# SERIALIO.net
KiCad netlist of a schematic drawn in Altium Designer
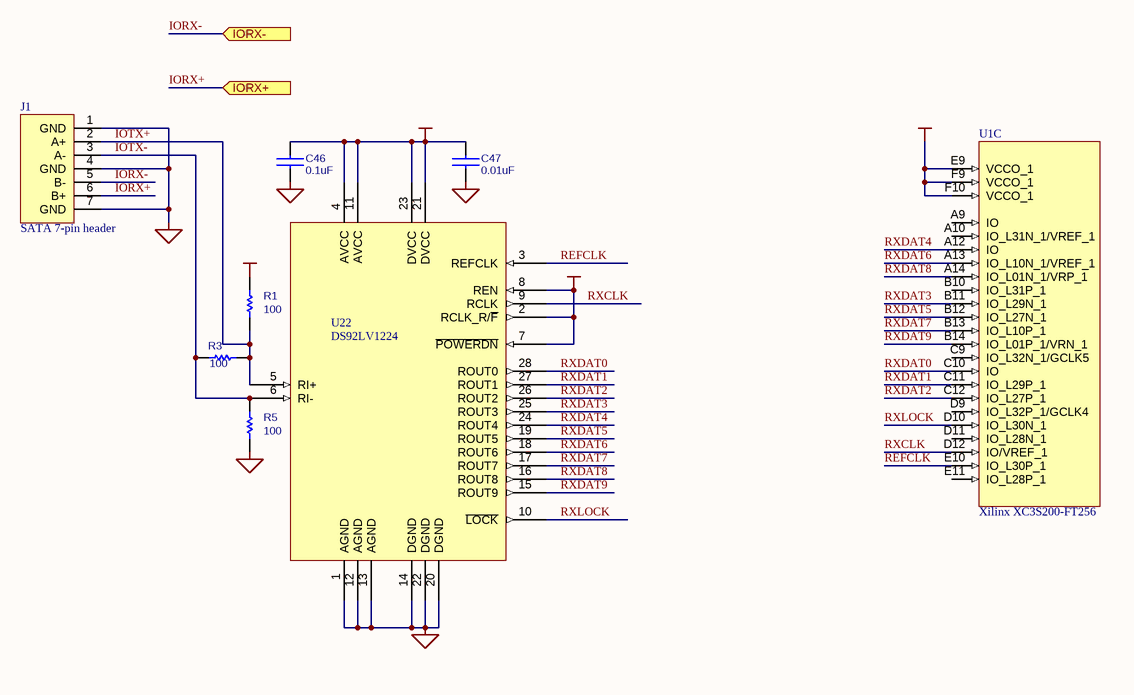
[diagram p0: SERIALIO.SCHDOC]

(export (version "E")
  (design (tool "Eeschema 10.0.6"))
  (components
    (comp (ref "C46")
      (value "0.1uF")
      (footprint "0603")
      (description "Standard Capacitor")
      (fields (field (name "Comment") "CAPACITOR"))
      (libsource (lib "parts") (part "CAPACITOR"))
    )
    (comp (ref "C47")
      (value "0.01uF")
      (footprint "0402")
      (description "Standard Capacitor")
      (fields (field (name "Comment") "CAPACITOR"))
      (libsource (lib "parts") (part "CAPACITOR"))
    )
    (comp (ref "J1")
      (value "SATA 7-pin header")
      (footprint "MOLES 67800-5005")
      (libsource (lib "parts") (part "SATA-7"))
    )
    (comp (ref "R1")
      (value "100")
      (footprint "0603")
      (description "Standard Passive Resistor")
      (fields (field (name "TOLERANCE") "1%"))
      (libsource (lib "parts") (part "RESISTOR"))
    )
    (comp (ref "R3")
      (value "100")
      (footprint "0603")
      (description "Standard Passive Resistor")
      (fields (field (name "TOLERANCE") "1%"))
      (libsource (lib "parts") (part "RESISTOR"))
    )
    (comp (ref "R5")
      (value "100")
      (footprint "0603")
      (description "Standard Passive Resistor")
      (fields (field (name "TOLERANCE") "1%"))
      (libsource (lib "parts") (part "RESISTOR"))
    )
    (comp (ref "U1")
      (value "Xilinx XC3S200-FT256")
      (footprint "Xilinx FT256 BGA")
      (description "Xilinx Spartan-3 FPGA")
      (libsource (lib "parts") (part "XC3S200-FT256"))
    )
    (comp (ref "U22")
      (value "DS92LV1224")
      (footprint "SSO-G28/E4.3")
      (description "30-66 MHz 10-Bit Bus LVDS Deserializer")
      (libsource (lib "parts") (part "DS92LV1224"))
    )
  )
  (nets
    (net (code "1") (name "/IORX+") (class "Default")
      (node (ref "J1") (pin "6") (pinfunction "B+_6") (pintype "passive"))
    )
    (net (code "2") (name "/IORX-") (class "Default")
      (node (ref "J1") (pin "5") (pinfunction "B-_5") (pintype "passive"))
    )
    (net (code "3") (name "/IOTX+") (class "Default")
      (node (ref "J1") (pin "2") (pinfunction "A+_2") (pintype "passive"))
      (node (ref "R1") (pin "2") (pintype "passive"))
      (node (ref "R3") (pin "2") (pintype "passive"))
      (node (ref "U22") (pin "5") (pinfunction "RI+_5") (pintype "input"))
    )
    (net (code "4") (name "/IOTX-") (class "Default")
      (node (ref "J1") (pin "3") (pinfunction "A-_3") (pintype "passive"))
      (node (ref "R3") (pin "1") (pintype "passive"))
      (node (ref "R5") (pin "2") (pintype "passive"))
      (node (ref "U22") (pin "6") (pinfunction "RI-_6") (pintype "input"))
    )
    (net (code "5") (name "/REFCLK") (class "Default")
      (node (ref "U1") (pin "E10") (pinfunction "IO_L30P_1_E10") (pintype "input"))
      (node (ref "U22") (pin "3") (pinfunction "REFCLK_3") (pintype "input"))
    )
    (net (code "6") (name "/RXCLK") (class "Default")
      (node (ref "U1") (pin "D12") (pinfunction "IO/VREF_1_D12") (pintype "input"))
      (node (ref "U22") (pin "9") (pinfunction "RCLK_9") (pintype "output"))
    )
    (net (code "7") (name "/RXDAT0") (class "Default")
      (node (ref "U1") (pin "C10") (pinfunction "IO_C10") (pintype "input"))
      (node (ref "U22") (pin "28") (pinfunction "ROUT0_28") (pintype "output"))
    )
    (net (code "8") (name "/RXDAT1") (class "Default")
      (node (ref "U1") (pin "C11") (pinfunction "IO_L29P_1_C11") (pintype "input"))
      (node (ref "U22") (pin "27") (pinfunction "ROUT1_27") (pintype "output"))
    )
    (net (code "9") (name "/RXDAT2") (class "Default")
      (node (ref "U1") (pin "C12") (pinfunction "IO_L27P_1_C12") (pintype "input"))
      (node (ref "U22") (pin "26") (pinfunction "ROUT2_26") (pintype "output"))
    )
    (net (code "10") (name "/RXDAT3") (class "Default")
      (node (ref "U1") (pin "B11") (pinfunction "IO_L29N_1_B11") (pintype "input"))
      (node (ref "U22") (pin "25") (pinfunction "ROUT3_25") (pintype "output"))
    )
    (net (code "11") (name "/RXDAT4") (class "Default")
      (node (ref "U1") (pin "A12") (pinfunction "IO_A12") (pintype "input"))
      (node (ref "U22") (pin "24") (pinfunction "ROUT4_24") (pintype "output"))
    )
    (net (code "12") (name "/RXDAT5") (class "Default")
      (node (ref "U1") (pin "B12") (pinfunction "IO_L27N_1_B12") (pintype "input"))
      (node (ref "U22") (pin "19") (pinfunction "ROUT5_19") (pintype "output"))
    )
    (net (code "13") (name "/RXDAT6") (class "Default")
      (node (ref "U1") (pin "A13") (pinfunction "IO_L10N_1/VREF_1_A13") (pintype "input"))
      (node (ref "U22") (pin "18") (pinfunction "ROUT6_18") (pintype "output"))
    )
    (net (code "14") (name "/RXDAT7") (class "Default")
      (node (ref "U1") (pin "B13") (pinfunction "IO_L10P_1_B13") (pintype "input"))
      (node (ref "U22") (pin "17") (pinfunction "ROUT7_17") (pintype "output"))
    )
    (net (code "15") (name "/RXDAT8") (class "Default")
      (node (ref "U1") (pin "A14") (pinfunction "IO_L01N_1/VRP_1_A14") (pintype "input"))
      (node (ref "U22") (pin "16") (pinfunction "ROUT8_16") (pintype "output"))
    )
    (net (code "16") (name "/RXDAT9") (class "Default")
      (node (ref "U1") (pin "B14") (pinfunction "IO_L01P_1/VRN_1_B14") (pintype "input"))
      (node (ref "U22") (pin "15") (pinfunction "ROUT9_15") (pintype "output"))
    )
    (net (code "17") (name "/RXLOCK") (class "Default")
      (node (ref "U1") (pin "D10") (pinfunction "IO_L30N_1_D10") (pintype "input"))
      (node (ref "U22") (pin "10") (pinfunction "~{LOCK}_10") (pintype "output"))
    )
    (net (code "18") (name "GND") (class "Default")
      (node (ref "C46") (pin "1") (pintype "passive"))
      (node (ref "C47") (pin "1") (pintype "passive"))
      (node (ref "J1") (pin "1") (pinfunction "GND_1") (pintype "passive"))
      (node (ref "J1") (pin "4") (pinfunction "GND_4") (pintype "passive"))
      (node (ref "J1") (pin "7") (pinfunction "GND_7") (pintype "passive"))
      (node (ref "R5") (pin "1") (pintype "passive"))
      (node (ref "U22") (pin "1") (pinfunction "AGND_1") (pintype "power_in"))
      (node (ref "U22") (pin "12") (pinfunction "AGND_12") (pintype "power_in"))
      (node (ref "U22") (pin "13") (pinfunction "AGND_13") (pintype "power_in"))
      (node (ref "U22") (pin "14") (pinfunction "DGND_14") (pintype "power_in"))
      (node (ref "U22") (pin "20") (pinfunction "DGND_20") (pintype "power_in"))
      (node (ref "U22") (pin "22") (pinfunction "DGND_22") (pintype "power_in"))
    )
    (net (code "19") (name "VCC") (class "Default")
      (node (ref "C46") (pin "2") (pintype "passive"))
      (node (ref "C47") (pin "2") (pintype "passive"))
      (node (ref "R1") (pin "1") (pintype "passive"))
      (node (ref "U1") (pin "E9") (pinfunction "VCCO_1_E9") (pintype "input"))
      (node (ref "U1") (pin "F10") (pinfunction "VCCO_1_F10") (pintype "input"))
      (node (ref "U1") (pin "F9") (pinfunction "VCCO_1_F9") (pintype "input"))
      (node (ref "U22") (pin "11") (pinfunction "AVCC_11") (pintype "power_in"))
      (node (ref "U22") (pin "2") (pinfunction "RCLK_R/~{F}_2") (pintype "output"))
      (node (ref "U22") (pin "21") (pinfunction "DVCC_21") (pintype "power_in"))
      (node (ref "U22") (pin "23") (pinfunction "DVCC_23") (pintype "power_in"))
      (node (ref "U22") (pin "4") (pinfunction "AVCC_4") (pintype "power_in"))
      (node (ref "U22") (pin "7") (pinfunction "~{POWERDN}_7") (pintype "input"))
      (node (ref "U22") (pin "8") (pinfunction "REN_8") (pintype "input"))
    )
    (net (code "20") (name "unconnected-(U1C-IO-PadA9)") (class "Default")
      (node (ref "U1") (pin "A9") (pinfunction "IO_A9") (pintype "input"))
    )
    (net (code "21") (name "unconnected-(U1C-IO_L28N_1-PadD11)") (class "Default")
      (node (ref "U1") (pin "D11") (pinfunction "IO_L28N_1_D11") (pintype "input"))
    )
    (net (code "22") (name "unconnected-(U1C-IO_L28P_1-PadE11)") (class "Default")
      (node (ref "U1") (pin "E11") (pinfunction "IO_L28P_1_E11") (pintype "input"))
    )
    (net (code "23") (name "unconnected-(U1C-IO_L31N_1{slash}VREF_1-PadA10)") (class "Default")
      (node (ref "U1") (pin "A10") (pinfunction "IO_L31N_1/VREF_1_A10") (pintype "input"))
    )
    (net (code "24") (name "unconnected-(U1C-IO_L31P_1-PadB10)") (class "Default")
      (node (ref "U1") (pin "B10") (pinfunction "IO_L31P_1_B10") (pintype "input"))
    )
    (net (code "25") (name "unconnected-(U1C-IO_L32N_1{slash}GCLK5-PadC9)") (class "Default")
      (node (ref "U1") (pin "C9") (pinfunction "IO_L32N_1/GCLK5_C9") (pintype "input"))
    )
    (net (code "26") (name "unconnected-(U1C-IO_L32P_1{slash}GCLK4-PadD9)") (class "Default")
      (node (ref "U1") (pin "D9") (pinfunction "IO_L32P_1/GCLK4_D9") (pintype "input"))
    )
  )
)
